# word_clock.net
KiCad netlist of a schematic drawn in EAGLE
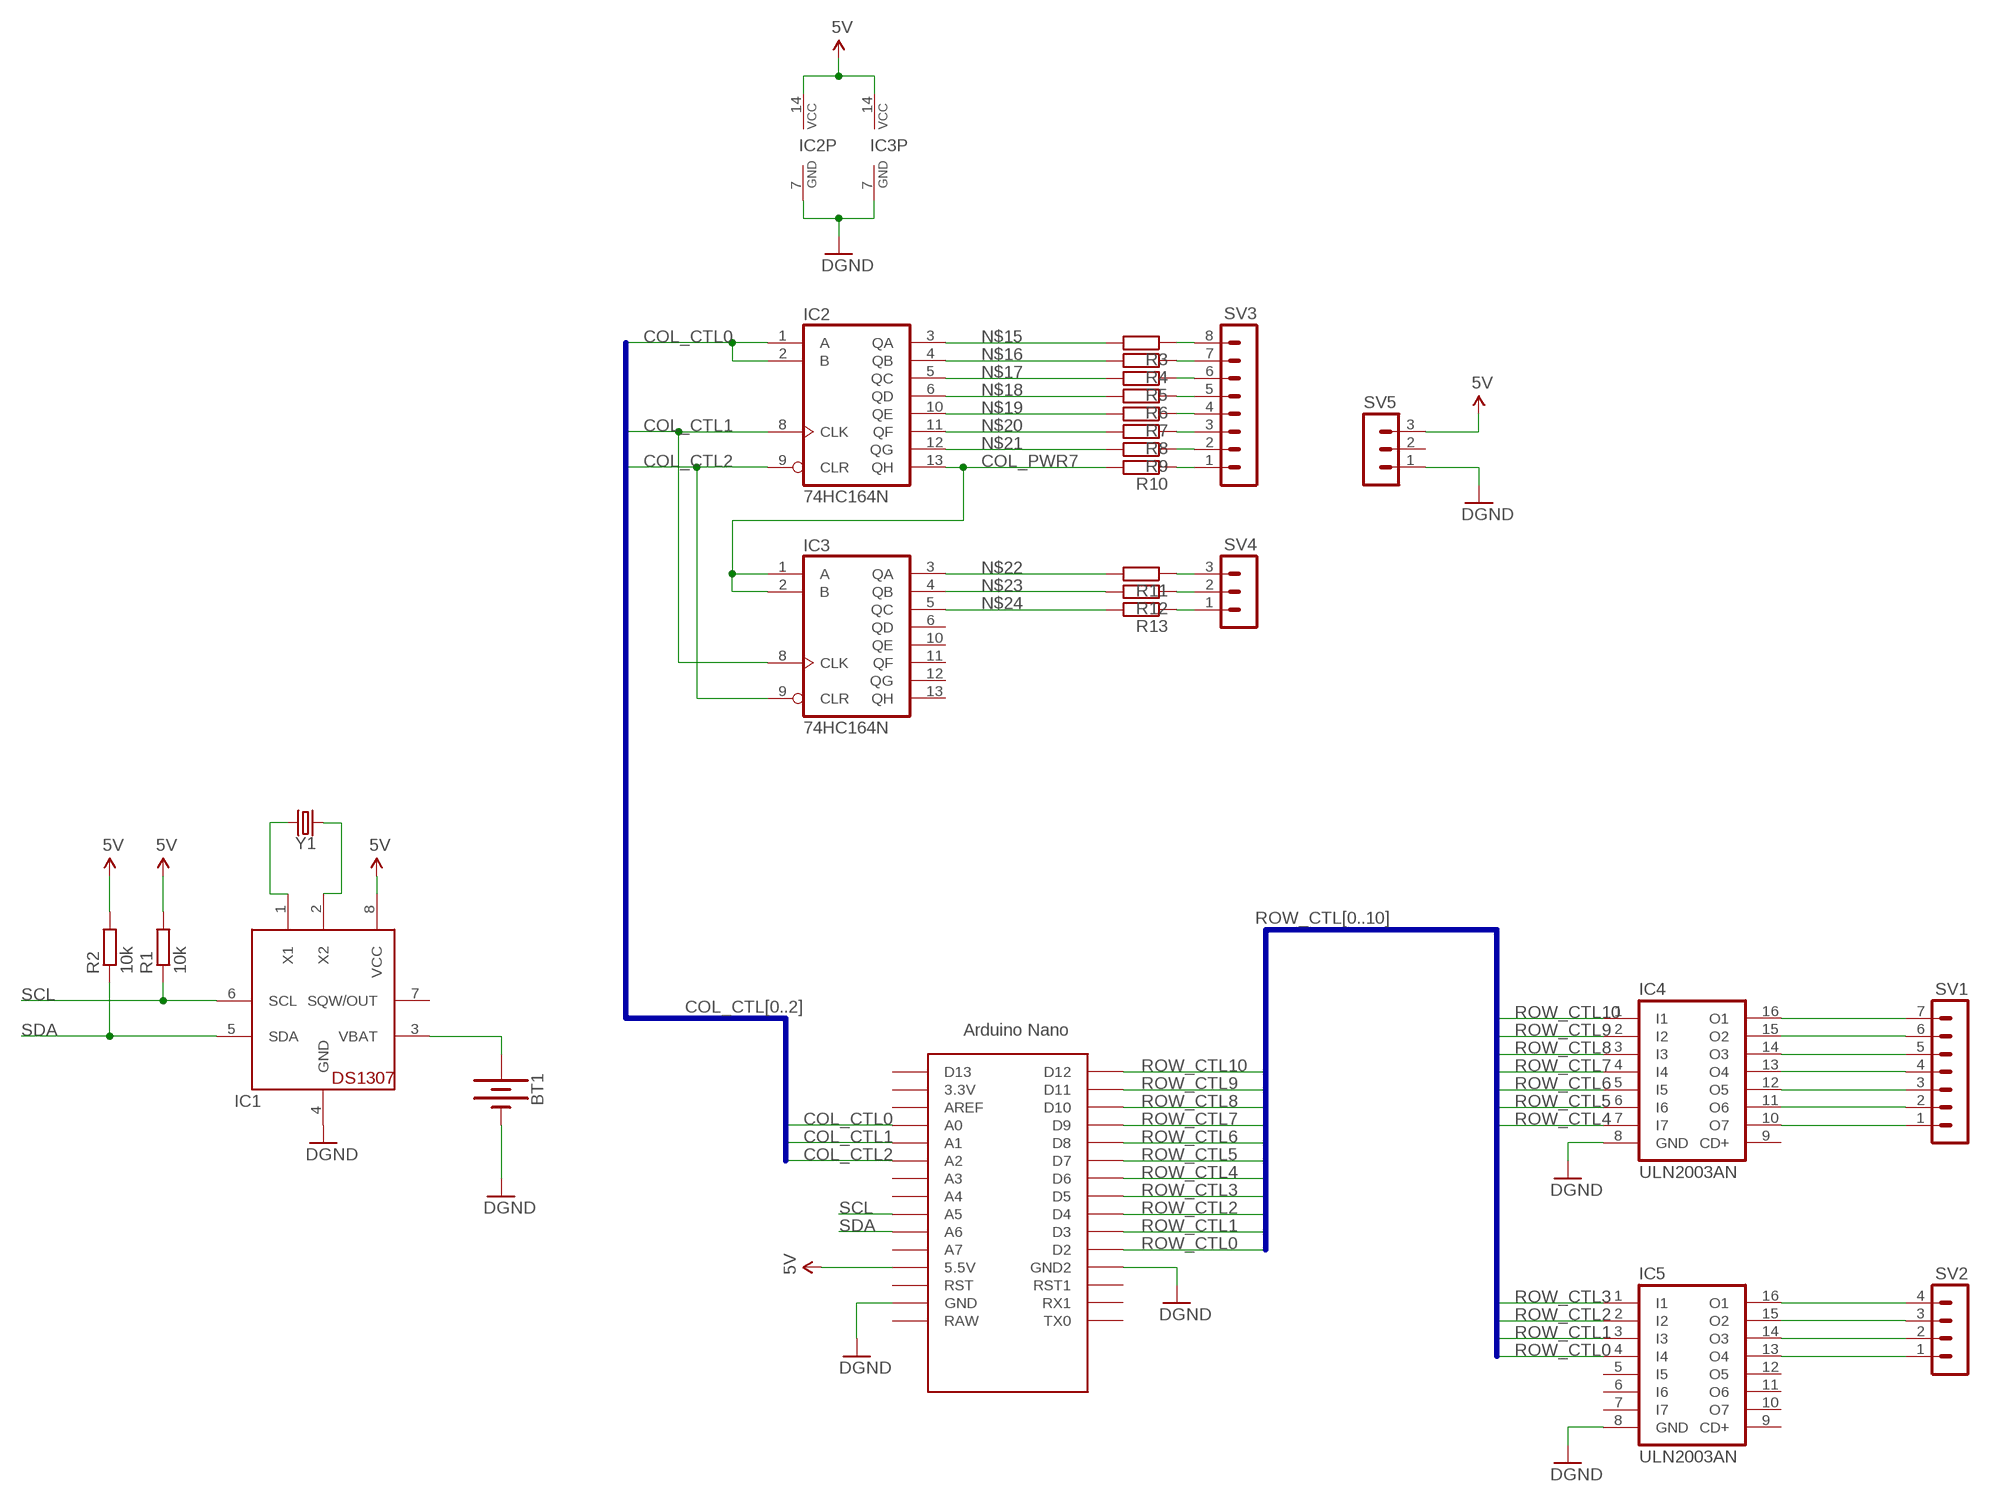
[diagram p0: schematic, sheet 1]

(export (version "E")
  (design (tool "Eeschema 10.0.6"))
  (components
    (comp (ref "BT1")
      (value "BATTERY-20MM_PTH")
      (footprint "eagle-import:BATTCOM_20MM_PTH")
      (libsource (lib "eagle-import") (part "BATTERY-20MM_PTH"))
    )
    (comp (ref "IC1")
      (value "DS1307")
      (footprint "eagle-import:DIL08")
      (libsource (lib "eagle-import") (part "DS1307"))
    )
    (comp (ref "IC2")
      (value "74HC164N")
      (footprint "eagle-import:DIL14")
      (libsource (lib "eagle-import") (part "74164NHC"))
    )
    (comp (ref "IC3")
      (value "74HC164N")
      (footprint "eagle-import:DIL14")
      (libsource (lib "eagle-import") (part "74164NHC"))
    )
    (comp (ref "IC4")
      (value "ULN2003AN")
      (footprint "eagle-import:DIL16")
      (libsource (lib "eagle-import") (part "ULN2003AN"))
    )
    (comp (ref "IC5")
      (value "ULN2003AN")
      (footprint "eagle-import:DIL16")
      (libsource (lib "eagle-import") (part "ULN2003AN"))
    )
    (comp (ref "R1")
      (value "10k")
      (footprint "eagle-import:0207_10")
      (libsource (lib "eagle-import") (part "R-EU_0207/10"))
    )
    (comp (ref "R2")
      (value "10k")
      (footprint "eagle-import:0207_10")
      (libsource (lib "eagle-import") (part "R-EU_0207/10"))
    )
    (comp (ref "R3")
      (value "R-EU_0207/10")
      (footprint "eagle-import:0207_10")
      (libsource (lib "eagle-import") (part "R-EU_0207/10"))
    )
    (comp (ref "R4")
      (value "R-EU_0207/10")
      (footprint "eagle-import:0207_10")
      (libsource (lib "eagle-import") (part "R-EU_0207/10"))
    )
    (comp (ref "R5")
      (value "R-EU_0207/10")
      (footprint "eagle-import:0207_10")
      (libsource (lib "eagle-import") (part "R-EU_0207/10"))
    )
    (comp (ref "R6")
      (value "R-EU_0207/10")
      (footprint "eagle-import:0207_10")
      (libsource (lib "eagle-import") (part "R-EU_0207/10"))
    )
    (comp (ref "R7")
      (value "R-EU_0207/10")
      (footprint "eagle-import:0207_10")
      (libsource (lib "eagle-import") (part "R-EU_0207/10"))
    )
    (comp (ref "R8")
      (value "R-EU_0207/10")
      (footprint "eagle-import:0207_10")
      (libsource (lib "eagle-import") (part "R-EU_0207/10"))
    )
    (comp (ref "R9")
      (value "R-EU_0207/10")
      (footprint "eagle-import:0207_10")
      (libsource (lib "eagle-import") (part "R-EU_0207/10"))
    )
    (comp (ref "R10")
      (value "R-EU_0207/10")
      (footprint "eagle-import:0207_10")
      (libsource (lib "eagle-import") (part "R-EU_0207/10"))
    )
    (comp (ref "R11")
      (value "R-EU_0207/10")
      (footprint "eagle-import:0207_10")
      (libsource (lib "eagle-import") (part "R-EU_0207/10"))
    )
    (comp (ref "R12")
      (value "R-EU_0207/10")
      (footprint "eagle-import:0207_10")
      (libsource (lib "eagle-import") (part "R-EU_0207/10"))
    )
    (comp (ref "R13")
      (value "R-EU_0207/10")
      (footprint "eagle-import:0207_10")
      (libsource (lib "eagle-import") (part "R-EU_0207/10"))
    )
    (comp (ref "SV1")
      (value "MA07-1")
      (footprint "eagle-import:MA07-1")
      (libsource (lib "eagle-import") (part "MA07-1"))
    )
    (comp (ref "SV2")
      (value "MA04-1")
      (footprint "eagle-import:MA04-1")
      (libsource (lib "eagle-import") (part "MA04-1"))
    )
    (comp (ref "SV3")
      (value "MA08-1")
      (footprint "eagle-import:MA08-1")
      (libsource (lib "eagle-import") (part "MA08-1"))
    )
    (comp (ref "SV4")
      (value "MA03-1")
      (footprint "eagle-import:MA03-1")
      (libsource (lib "eagle-import") (part "MA03-1"))
    )
    (comp (ref "SV5")
      (value "MA03-1")
      (footprint "eagle-import:MA03-1")
      (libsource (lib "eagle-import") (part "MA03-1"))
    )
    (comp (ref "U$1")
      (value "NANO_SHIELD")
      (footprint "eagle-import:NANO_SHIELD")
      (libsource (lib "eagle-import") (part "NANO_SHIELD"))
    )
    (comp (ref "Y1")
      (value "CRYSTALPTH-3X8")
      (footprint "eagle-import:CRYSTAL-PTH-3X8-CYL")
      (libsource (lib "eagle-import") (part "CRYSTALPTH-3X8"))
    )
  )
  (nets
    (net (code "1") (name "/COL_CTL0") (class "Default")
      (node (ref "IC2") (pin "1") (pinfunction "A_1") (pintype "input"))
      (node (ref "IC2") (pin "2") (pinfunction "B_2") (pintype "input"))
      (node (ref "U$1") (pin "A0") (pinfunction "A0_A0") (pintype "bidirectional"))
    )
    (net (code "2") (name "/COL_CTL1") (class "Default")
      (node (ref "IC2") (pin "8") (pinfunction "CLK_8") (pintype "input"))
      (node (ref "IC3") (pin "8") (pinfunction "CLK_8") (pintype "input"))
      (node (ref "U$1") (pin "A1") (pinfunction "A1_A1") (pintype "bidirectional"))
    )
    (net (code "3") (name "/COL_CTL2") (class "Default")
      (node (ref "IC2") (pin "9") (pinfunction "CLR_9") (pintype "input"))
      (node (ref "IC3") (pin "9") (pinfunction "CLR_9") (pintype "input"))
      (node (ref "U$1") (pin "A2") (pinfunction "A2_A2") (pintype "bidirectional"))
    )
    (net (code "5") (name "/COL_PWR7") (class "Default")
      (node (ref "IC2") (pin "13") (pinfunction "QH_13") (pintype "output"))
      (node (ref "IC3") (pin "1") (pinfunction "A_1") (pintype "input"))
      (node (ref "IC3") (pin "2") (pinfunction "B_2") (pintype "input"))
      (node (ref "R10") (pin "2") (pinfunction "2_2") (pintype "passive"))
    )
    (net (code "6") (name "/N$15") (class "Default")
      (node (ref "IC2") (pin "3") (pinfunction "QA_3") (pintype "output"))
      (node (ref "R3") (pin "2") (pinfunction "2_2") (pintype "passive"))
    )
    (net (code "7") (name "/N$16") (class "Default")
      (node (ref "IC2") (pin "4") (pinfunction "QB_4") (pintype "output"))
      (node (ref "R4") (pin "2") (pinfunction "2_2") (pintype "passive"))
    )
    (net (code "8") (name "/N$17") (class "Default")
      (node (ref "IC2") (pin "5") (pinfunction "QC_5") (pintype "output"))
      (node (ref "R5") (pin "2") (pinfunction "2_2") (pintype "passive"))
    )
    (net (code "9") (name "/N$18") (class "Default")
      (node (ref "IC2") (pin "6") (pinfunction "QD_6") (pintype "output"))
      (node (ref "R6") (pin "2") (pinfunction "2_2") (pintype "passive"))
    )
    (net (code "10") (name "/N$19") (class "Default")
      (node (ref "IC2") (pin "10") (pinfunction "QE_10") (pintype "output"))
      (node (ref "R7") (pin "2") (pinfunction "2_2") (pintype "passive"))
    )
    (net (code "11") (name "/N$20") (class "Default")
      (node (ref "IC2") (pin "11") (pinfunction "QF_11") (pintype "output"))
      (node (ref "R8") (pin "2") (pinfunction "2_2") (pintype "passive"))
    )
    (net (code "12") (name "/N$21") (class "Default")
      (node (ref "IC2") (pin "12") (pinfunction "QG_12") (pintype "output"))
      (node (ref "R9") (pin "2") (pinfunction "2_2") (pintype "passive"))
    )
    (net (code "13") (name "/N$22") (class "Default")
      (node (ref "IC3") (pin "3") (pinfunction "QA_3") (pintype "output"))
      (node (ref "R11") (pin "2") (pinfunction "2_2") (pintype "passive"))
    )
    (net (code "14") (name "/N$23") (class "Default")
      (node (ref "IC3") (pin "4") (pinfunction "QB_4") (pintype "output"))
      (node (ref "R12") (pin "2") (pinfunction "2_2") (pintype "passive"))
    )
    (net (code "15") (name "/N$24") (class "Default")
      (node (ref "IC3") (pin "5") (pinfunction "QC_5") (pintype "output"))
      (node (ref "R13") (pin "2") (pinfunction "2_2") (pintype "passive"))
    )
    (net (code "16") (name "/ROW_CTL0") (class "Default")
      (node (ref "IC5") (pin "4") (pinfunction "I4_4") (pintype "input"))
      (node (ref "U$1") (pin "D2") (pinfunction "D2_D2") (pintype "bidirectional"))
    )
    (net (code "17") (name "/ROW_CTL1") (class "Default")
      (node (ref "IC5") (pin "3") (pinfunction "I3_3") (pintype "input"))
      (node (ref "U$1") (pin "D3") (pinfunction "D3_D3") (pintype "bidirectional"))
    )
    (net (code "18") (name "/ROW_CTL2") (class "Default")
      (node (ref "IC5") (pin "2") (pinfunction "I2_2") (pintype "input"))
      (node (ref "U$1") (pin "D4") (pinfunction "D4_D4") (pintype "bidirectional"))
    )
    (net (code "19") (name "/ROW_CTL3") (class "Default")
      (node (ref "IC5") (pin "1") (pinfunction "I1_1") (pintype "input"))
      (node (ref "U$1") (pin "D5") (pinfunction "D5_D5") (pintype "bidirectional"))
    )
    (net (code "20") (name "/ROW_CTL4") (class "Default")
      (node (ref "IC4") (pin "7") (pinfunction "I7_7") (pintype "input"))
      (node (ref "U$1") (pin "D6") (pinfunction "D6_D6") (pintype "bidirectional"))
    )
    (net (code "21") (name "/ROW_CTL5") (class "Default")
      (node (ref "IC4") (pin "6") (pinfunction "I6_6") (pintype "input"))
      (node (ref "U$1") (pin "D7") (pinfunction "D7_D7") (pintype "bidirectional"))
    )
    (net (code "22") (name "/ROW_CTL6") (class "Default")
      (node (ref "IC4") (pin "5") (pinfunction "I5_5") (pintype "input"))
      (node (ref "U$1") (pin "D8") (pinfunction "D8_D8") (pintype "bidirectional"))
    )
    (net (code "23") (name "/ROW_CTL7") (class "Default")
      (node (ref "IC4") (pin "4") (pinfunction "I4_4") (pintype "input"))
      (node (ref "U$1") (pin "D9") (pinfunction "D9_D9") (pintype "bidirectional"))
    )
    (net (code "24") (name "/ROW_CTL8") (class "Default")
      (node (ref "IC4") (pin "3") (pinfunction "I3_3") (pintype "input"))
      (node (ref "U$1") (pin "D10") (pinfunction "D10_D10") (pintype "bidirectional"))
    )
    (net (code "25") (name "/ROW_CTL9") (class "Default")
      (node (ref "IC4") (pin "2") (pinfunction "I2_2") (pintype "input"))
      (node (ref "U$1") (pin "D11") (pinfunction "D11_D11") (pintype "bidirectional"))
    )
    (net (code "26") (name "/ROW_CTL10") (class "Default")
      (node (ref "IC4") (pin "1") (pinfunction "I1_1") (pintype "input"))
      (node (ref "U$1") (pin "D12") (pinfunction "D12_D12") (pintype "bidirectional"))
    )
    (net (code "28") (name "/SCL") (class "Default")
      (node (ref "IC1") (pin "6") (pinfunction "SCL_6") (pintype "bidirectional"))
      (node (ref "R1") (pin "1") (pinfunction "1_1") (pintype "passive"))
      (node (ref "U$1") (pin "A5") (pinfunction "A5_A5") (pintype "bidirectional"))
    )
    (net (code "29") (name "/SDA") (class "Default")
      (node (ref "IC1") (pin "5") (pinfunction "SDA_5") (pintype "bidirectional"))
      (node (ref "R2") (pin "1") (pinfunction "1_1") (pintype "passive"))
      (node (ref "U$1") (pin "A6") (pinfunction "A6_A6") (pintype "bidirectional"))
    )
    (net (code "30") (name "5V") (class "Default")
      (node (ref "IC1") (pin "8") (pinfunction "VCC_8") (pintype "power_in"))
      (node (ref "IC2") (pin "14") (pinfunction "VCC_14") (pintype "power_in"))
      (node (ref "IC3") (pin "14") (pinfunction "VCC_14") (pintype "power_in"))
      (node (ref "R1") (pin "2") (pinfunction "2_2") (pintype "passive"))
      (node (ref "R2") (pin "2") (pinfunction "2_2") (pintype "passive"))
      (node (ref "SV5") (pin "3") (pinfunction "3_3") (pintype "passive"))
      (node (ref "U$1") (pin "5V") (pinfunction "5.5V_5V") (pintype "bidirectional"))
    )
    (net (code "31") (name "DGND") (class "Default")
      (node (ref "BT1") (pin "2") (pinfunction "-_2") (pintype "power_in"))
      (node (ref "IC1") (pin "4") (pinfunction "GND_4") (pintype "power_in"))
      (node (ref "IC2") (pin "7") (pinfunction "GND_7") (pintype "power_in"))
      (node (ref "IC3") (pin "7") (pinfunction "GND_7") (pintype "power_in"))
      (node (ref "IC4") (pin "8") (pinfunction "GND_8") (pintype "power_in"))
      (node (ref "IC5") (pin "8") (pinfunction "GND_8") (pintype "power_in"))
      (node (ref "SV5") (pin "1") (pinfunction "1_1") (pintype "passive"))
      (node (ref "U$1") (pin "GND") (pinfunction "GND_GND") (pintype "bidirectional"))
      (node (ref "U$1") (pin "GND1") (pinfunction "GND2_GND1") (pintype "bidirectional"))
    )
    (net (code "32") (name "Net-(BT1-+)") (class "Default")
      (node (ref "BT1") (pin "1") (pinfunction "+_1") (pintype "power_in"))
      (node (ref "IC1") (pin "3") (pinfunction "VBAT_3") (pintype "power_in"))
    )
    (net (code "33") (name "Net-(IC1-X1)") (class "Default")
      (node (ref "IC1") (pin "1") (pinfunction "X1_1") (pintype "passive"))
      (node (ref "Y1") (pin "2") (pinfunction "2_2") (pintype "passive"))
    )
    (net (code "34") (name "Net-(IC1-X2)") (class "Default")
      (node (ref "IC1") (pin "2") (pinfunction "X2_2") (pintype "passive"))
      (node (ref "Y1") (pin "1") (pinfunction "1_1") (pintype "passive"))
    )
    (net (code "35") (name "Net-(IC4-O1)") (class "Default")
      (node (ref "IC4") (pin "16") (pinfunction "O1_16") (pintype "open_collector"))
      (node (ref "SV1") (pin "7") (pinfunction "7_7") (pintype "passive"))
    )
    (net (code "36") (name "Net-(IC4-O2)") (class "Default")
      (node (ref "IC4") (pin "15") (pinfunction "O2_15") (pintype "open_collector"))
      (node (ref "SV1") (pin "6") (pinfunction "6_6") (pintype "passive"))
    )
    (net (code "37") (name "Net-(IC4-O3)") (class "Default")
      (node (ref "IC4") (pin "14") (pinfunction "O3_14") (pintype "open_collector"))
      (node (ref "SV1") (pin "5") (pinfunction "5_5") (pintype "passive"))
    )
    (net (code "38") (name "Net-(IC4-O4)") (class "Default")
      (node (ref "IC4") (pin "13") (pinfunction "O4_13") (pintype "open_collector"))
      (node (ref "SV1") (pin "4") (pinfunction "4_4") (pintype "passive"))
    )
    (net (code "39") (name "Net-(IC4-O5)") (class "Default")
      (node (ref "IC4") (pin "12") (pinfunction "O5_12") (pintype "open_collector"))
      (node (ref "SV1") (pin "3") (pinfunction "3_3") (pintype "passive"))
    )
    (net (code "40") (name "Net-(IC4-O6)") (class "Default")
      (node (ref "IC4") (pin "11") (pinfunction "O6_11") (pintype "open_collector"))
      (node (ref "SV1") (pin "2") (pinfunction "2_2") (pintype "passive"))
    )
    (net (code "41") (name "Net-(IC4-O7)") (class "Default")
      (node (ref "IC4") (pin "10") (pinfunction "O7_10") (pintype "open_collector"))
      (node (ref "SV1") (pin "1") (pinfunction "1_1") (pintype "passive"))
    )
    (net (code "42") (name "Net-(IC5-O1)") (class "Default")
      (node (ref "IC5") (pin "16") (pinfunction "O1_16") (pintype "open_collector"))
      (node (ref "SV2") (pin "4") (pinfunction "4_4") (pintype "passive"))
    )
    (net (code "43") (name "Net-(IC5-O2)") (class "Default")
      (node (ref "IC5") (pin "15") (pinfunction "O2_15") (pintype "open_collector"))
      (node (ref "SV2") (pin "3") (pinfunction "3_3") (pintype "passive"))
    )
    (net (code "44") (name "Net-(IC5-O3)") (class "Default")
      (node (ref "IC5") (pin "14") (pinfunction "O3_14") (pintype "open_collector"))
      (node (ref "SV2") (pin "2") (pinfunction "2_2") (pintype "passive"))
    )
    (net (code "45") (name "Net-(IC5-O4)") (class "Default")
      (node (ref "IC5") (pin "13") (pinfunction "O4_13") (pintype "open_collector"))
      (node (ref "SV2") (pin "1") (pinfunction "1_1") (pintype "passive"))
    )
    (net (code "46") (name "Net-(R3-Pad1)") (class "Default")
      (node (ref "R3") (pin "1") (pinfunction "1_1") (pintype "passive"))
      (node (ref "SV3") (pin "8") (pinfunction "8_8") (pintype "passive"))
    )
    (net (code "47") (name "Net-(R4-Pad1)") (class "Default")
      (node (ref "R4") (pin "1") (pinfunction "1_1") (pintype "passive"))
      (node (ref "SV3") (pin "7") (pinfunction "7_7") (pintype "passive"))
    )
    (net (code "48") (name "Net-(R5-Pad1)") (class "Default")
      (node (ref "R5") (pin "1") (pinfunction "1_1") (pintype "passive"))
      (node (ref "SV3") (pin "6") (pinfunction "6_6") (pintype "passive"))
    )
    (net (code "49") (name "Net-(R6-Pad1)") (class "Default")
      (node (ref "R6") (pin "1") (pinfunction "1_1") (pintype "passive"))
      (node (ref "SV3") (pin "5") (pinfunction "5_5") (pintype "passive"))
    )
    (net (code "50") (name "Net-(R7-Pad1)") (class "Default")
      (node (ref "R7") (pin "1") (pinfunction "1_1") (pintype "passive"))
      (node (ref "SV3") (pin "4") (pinfunction "4_4") (pintype "passive"))
    )
    (net (code "51") (name "Net-(R8-Pad1)") (class "Default")
      (node (ref "R8") (pin "1") (pinfunction "1_1") (pintype "passive"))
      (node (ref "SV3") (pin "3") (pinfunction "3_3") (pintype "passive"))
    )
    (net (code "52") (name "Net-(R9-Pad1)") (class "Default")
      (node (ref "R9") (pin "1") (pinfunction "1_1") (pintype "passive"))
      (node (ref "SV3") (pin "2") (pinfunction "2_2") (pintype "passive"))
    )
    (net (code "53") (name "Net-(R10-Pad1)") (class "Default")
      (node (ref "R10") (pin "1") (pinfunction "1_1") (pintype "passive"))
      (node (ref "SV3") (pin "1") (pinfunction "1_1") (pintype "passive"))
    )
    (net (code "54") (name "Net-(R11-Pad1)") (class "Default")
      (node (ref "R11") (pin "1") (pinfunction "1_1") (pintype "passive"))
      (node (ref "SV4") (pin "3") (pinfunction "3_3") (pintype "passive"))
    )
    (net (code "55") (name "Net-(R12-Pad1)") (class "Default")
      (node (ref "R12") (pin "1") (pinfunction "1_1") (pintype "passive"))
      (node (ref "SV4") (pin "2") (pinfunction "2_2") (pintype "passive"))
    )
    (net (code "56") (name "Net-(R13-Pad1)") (class "Default")
      (node (ref "R13") (pin "1") (pinfunction "1_1") (pintype "passive"))
      (node (ref "SV4") (pin "1") (pinfunction "1_1") (pintype "passive"))
    )
    (net (code "57") (name "unconnected-(IC1-SQW{slash}OUT-Pad7)") (class "Default")
      (node (ref "IC1") (pin "7") (pinfunction "SQW/OUT_7") (pintype "bidirectional"))
    )
    (net (code "58") (name "unconnected-(IC3A-QD-Pad6)") (class "Default")
      (node (ref "IC3") (pin "6") (pinfunction "QD_6") (pintype "output"))
    )
    (net (code "59") (name "unconnected-(IC3A-QE-Pad10)") (class "Default")
      (node (ref "IC3") (pin "10") (pinfunction "QE_10") (pintype "output"))
    )
    (net (code "60") (name "unconnected-(IC3A-QF-Pad11)") (class "Default")
      (node (ref "IC3") (pin "11") (pinfunction "QF_11") (pintype "output"))
    )
    (net (code "61") (name "unconnected-(IC3A-QG-Pad12)") (class "Default")
      (node (ref "IC3") (pin "12") (pinfunction "QG_12") (pintype "output"))
    )
    (net (code "62") (name "unconnected-(IC3A-QH-Pad13)") (class "Default")
      (node (ref "IC3") (pin "13") (pinfunction "QH_13") (pintype "output"))
    )
    (net (code "63") (name "unconnected-(IC4-CD+-Pad9)") (class "Default")
      (node (ref "IC4") (pin "9") (pinfunction "CD+_9") (pintype "passive"))
    )
    (net (code "64") (name "unconnected-(IC5-CD+-Pad9)") (class "Default")
      (node (ref "IC5") (pin "9") (pinfunction "CD+_9") (pintype "passive"))
    )
    (net (code "65") (name "unconnected-(IC5-I5-Pad5)") (class "Default")
      (node (ref "IC5") (pin "5") (pinfunction "I5_5") (pintype "input"))
    )
    (net (code "66") (name "unconnected-(IC5-I6-Pad6)") (class "Default")
      (node (ref "IC5") (pin "6") (pinfunction "I6_6") (pintype "input"))
    )
    (net (code "67") (name "unconnected-(IC5-I7-Pad7)") (class "Default")
      (node (ref "IC5") (pin "7") (pinfunction "I7_7") (pintype "input"))
    )
    (net (code "68") (name "unconnected-(IC5-O5-Pad12)") (class "Default")
      (node (ref "IC5") (pin "12") (pinfunction "O5_12") (pintype "open_collector"))
    )
    (net (code "69") (name "unconnected-(IC5-O6-Pad11)") (class "Default")
      (node (ref "IC5") (pin "11") (pinfunction "O6_11") (pintype "open_collector"))
    )
    (net (code "70") (name "unconnected-(IC5-O7-Pad10)") (class "Default")
      (node (ref "IC5") (pin "10") (pinfunction "O7_10") (pintype "open_collector"))
    )
    (net (code "71") (name "unconnected-(SV5-Pad2)") (class "Default")
      (node (ref "SV5") (pin "2") (pinfunction "2_2") (pintype "passive"))
    )
    (net (code "72") (name "unconnected-(U$1-Pad3.3V)") (class "Default")
      (node (ref "U$1") (pin "3.3V") (pinfunction "3.3V_3.3V") (pintype "bidirectional"))
    )
    (net (code "73") (name "unconnected-(U$1-PadA3)") (class "Default")
      (node (ref "U$1") (pin "A3") (pinfunction "A3_A3") (pintype "bidirectional"))
    )
    (net (code "74") (name "unconnected-(U$1-PadA4)") (class "Default")
      (node (ref "U$1") (pin "A4") (pinfunction "A4_A4") (pintype "bidirectional"))
    )
    (net (code "75") (name "unconnected-(U$1-PadA7)") (class "Default")
      (node (ref "U$1") (pin "A7") (pinfunction "A7_A7") (pintype "bidirectional"))
    )
    (net (code "76") (name "unconnected-(U$1-PadAREF)") (class "Default")
      (node (ref "U$1") (pin "AREF") (pinfunction "AREF_AREF") (pintype "bidirectional"))
    )
    (net (code "77") (name "unconnected-(U$1-PadD13)") (class "Default")
      (node (ref "U$1") (pin "D13") (pinfunction "D13_D13") (pintype "bidirectional"))
    )
    (net (code "78") (name "unconnected-(U$1-PadRAW)") (class "Default")
      (node (ref "U$1") (pin "RAW") (pinfunction "RAW_RAW") (pintype "bidirectional"))
    )
    (net (code "79") (name "unconnected-(U$1-PadRST)") (class "Default")
      (node (ref "U$1") (pin "RST") (pinfunction "RST_RST") (pintype "bidirectional"))
    )
    (net (code "80") (name "unconnected-(U$1-PadRST1)") (class "Default")
      (node (ref "U$1") (pin "RST1") (pinfunction "RST1_RST1") (pintype "bidirectional"))
    )
    (net (code "81") (name "unconnected-(U$1-PadRX1)") (class "Default")
      (node (ref "U$1") (pin "RX1") (pinfunction "RX1_RX1") (pintype "bidirectional"))
    )
    (net (code "82") (name "unconnected-(U$1-PadTX0)") (class "Default")
      (node (ref "U$1") (pin "TX0") (pinfunction "TX0_TX0") (pintype "bidirectional"))
    )
  )
)
